# Lily_Pad_VGA_Fly_v1_01.net
KiCad netlist of a schematic drawn in EAGLE
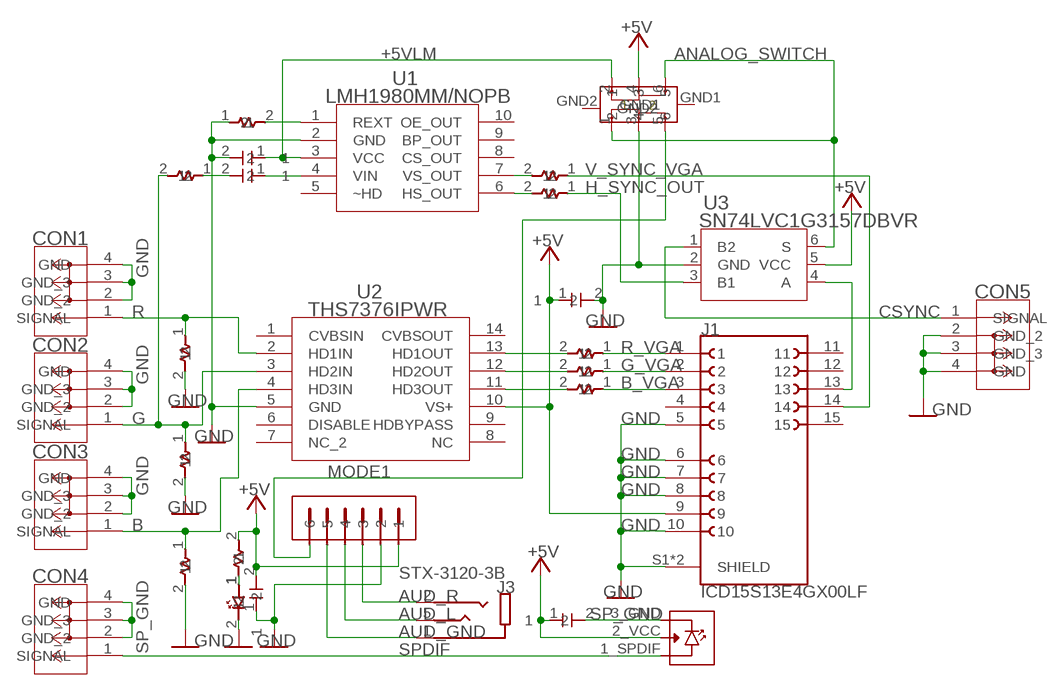
[diagram p0: schematic, sheet 1]

(export (version "E")
  (design (tool "Eeschema 10.0.6"))
  (components
    (comp (ref "C1")
      (value "22UF")
      (footprint "eagle-import:CAPACITOR_SMT_0603")
      (libsource (lib "eagle-import") (part "CAPACITOR0603"))
    )
    (comp (ref "C2")
      (value "0.1UF")
      (footprint "eagle-import:CAPACITOR_SMT_0603")
      (libsource (lib "eagle-import") (part "CAPACITOR0603"))
    )
    (comp (ref "C3")
      (value "0.1UF")
      (footprint "eagle-import:CAPACITOR_SMT_0603")
      (libsource (lib "eagle-import") (part "CAPACITOR0603"))
    )
    (comp (ref "C4")
      (value "0.1UF")
      (footprint "eagle-import:CAPACITOR_SMT_0603")
      (libsource (lib "eagle-import") (part "CAPACITOR0603"))
    )
    (comp (ref "C5")
      (value "0.1UF")
      (footprint "eagle-import:CAPACITOR_SMT_0603")
      (libsource (lib "eagle-import") (part "CAPACITOR0603"))
    )
    (comp (ref "CON1")
      (value "CONMHF1-SMD-G-T")
      (footprint "eagle-import:COAX3_CONMHF1-SMD-G-T_TEC")
      (fields (field (name "COPYRIGHT") "Copyright (C) 2024 Ultra Librarian. All rights reserved."))
      (libsource (lib "eagle-import") (part "CONMHF1-SMD-G-T"))
    )
    (comp (ref "CON2")
      (value "CONMHF1-SMD-G-T")
      (footprint "eagle-import:COAX3_CONMHF1-SMD-G-T_TEC")
      (fields (field (name "COPYRIGHT") "Copyright (C) 2024 Ultra Librarian. All rights reserved."))
      (libsource (lib "eagle-import") (part "CONMHF1-SMD-G-T"))
    )
    (comp (ref "CON3")
      (value "CONMHF1-SMD-G-T")
      (footprint "eagle-import:COAX3_CONMHF1-SMD-G-T_TEC")
      (fields (field (name "COPYRIGHT") "Copyright (C) 2024 Ultra Librarian. All rights reserved."))
      (libsource (lib "eagle-import") (part "CONMHF1-SMD-G-T"))
    )
    (comp (ref "CON4")
      (value "CONMHF1-SMD-G-T")
      (footprint "eagle-import:COAX3_CONMHF1-SMD-G-T_TEC")
      (fields (field (name "COPYRIGHT") "Copyright (C) 2024 Ultra Librarian. All rights reserved."))
      (libsource (lib "eagle-import") (part "CONMHF1-SMD-G-T"))
    )
    (comp (ref "CON5")
      (value "CONMHF1-SMD-G-T")
      (footprint "eagle-import:COAX3_CONMHF1-SMD-G-T_TEC")
      (fields (field (name "COPYRIGHT") "Copyright (C) 2024 Ultra Librarian. All rights reserved."))
      (libsource (lib "eagle-import") (part "CONMHF1-SMD-G-T"))
    )
    (comp (ref "J1")
      (value "ICD15S13E4GX00LF")
      (footprint "eagle-import:ICD15S13E4GX00LF")
      (fields (field (name "MANUFACTURER") "Amphenol"))
      (libsource (lib "eagle-import") (part "ICD15S13E4GX00LF"))
    )
    (comp (ref "J2")
      (value "0530470610")
      (footprint "eagle-import:0530470610")
      (libsource (lib "eagle-import") (part "0530470610"))
    )
    (comp (ref "J3")
      (value "STX-3120-3B")
      (footprint "eagle-import:KYCON_STX-3120-3B")
      (fields (field (name "MANUFACTURER") "KYCON"))
      (libsource (lib "eagle-import") (part "STX-3120-3B"))
    )
    (comp (ref "J4")
      (value "GQ-1504_OPTICAL")
      (footprint "eagle-import:GQ-1504_OPTICAL")
      (libsource (lib "eagle-import") (part "GQ-1504_OPTICAL"))
    )
    (comp (ref "LED1")
      (value "LED")
      (footprint "eagle-import:LED_SMT_0603")
      (libsource (lib "eagle-import") (part "LED"))
    )
    (comp (ref "R1")
      (value "75R")
      (footprint "eagle-import:RESISTOR_SMT_0603")
      (libsource (lib "eagle-import") (part "RESISTOR0603"))
    )
    (comp (ref "R2")
      (value "75R")
      (footprint "eagle-import:RESISTOR_SMT_0603")
      (libsource (lib "eagle-import") (part "RESISTOR0603"))
    )
    (comp (ref "R3")
      (value "75R")
      (footprint "eagle-import:RESISTOR_SMT_0603")
      (libsource (lib "eagle-import") (part "RESISTOR0603"))
    )
    (comp (ref "R4")
      (value "75R")
      (footprint "eagle-import:RESISTOR_SMT_0603")
      (libsource (lib "eagle-import") (part "RESISTOR0603"))
    )
    (comp (ref "R5")
      (value "75R")
      (footprint "eagle-import:RESISTOR_SMT_0603")
      (libsource (lib "eagle-import") (part "RESISTOR0603"))
    )
    (comp (ref "R6")
      (value "75R")
      (footprint "eagle-import:RESISTOR_SMT_0603")
      (libsource (lib "eagle-import") (part "RESISTOR0603"))
    )
    (comp (ref "R7")
      (value "91R")
      (footprint "eagle-import:RESISTOR_SMT_0603")
      (libsource (lib "eagle-import") (part "RESISTOR0603"))
    )
    (comp (ref "R8")
      (value "100R")
      (footprint "eagle-import:RESISTOR_SMT_0603")
      (libsource (lib "eagle-import") (part "RESISTOR0603"))
    )
    (comp (ref "R9")
      (value "100R")
      (footprint "eagle-import:RESISTOR_SMT_0603")
      (libsource (lib "eagle-import") (part "RESISTOR0603"))
    )
    (comp (ref "RA")
      (value "1K")
      (footprint "eagle-import:RESISTOR_SMT_0603")
      (libsource (lib "eagle-import") (part "RESISTOR0603"))
    )
    (comp (ref "RB")
      (value "10K")
      (footprint "eagle-import:RESISTOR_SMT_0603")
      (libsource (lib "eagle-import") (part "RESISTOR0603"))
    )
    (comp (ref "SW1")
      (value "DPDT_SW_SK22D07")
      (footprint "eagle-import:DPDT_SK22D07")
      (libsource (lib "eagle-import") (part "DPDT_SW_SK22D07"))
    )
    (comp (ref "U1")
      (value "LMH1980MM/NOPB")
      (footprint "eagle-import:MUB10A")
      (fields (field (name "COPYRIGHT") "Copyright (C) 2024 Ultra Librarian. All rights reserved."))
      (libsource (lib "eagle-import") (part "LMH1980MM/NOPB"))
    )
    (comp (ref "U2")
      (value "THS7376IPWR")
      (footprint "eagle-import:PW14_TEX")
      (fields (field (name "COPYRIGHT") "Copyright (C) 2024 Ultra Librarian. All rights reserved."))
      (libsource (lib "eagle-import") (part "THS7376IPWR"))
    )
    (comp (ref "U3")
      (value "SN74LVC1G3157DBVR")
      (footprint "eagle-import:DBV6")
      (fields (field (name "COPYRIGHT") "Copyright (C) 2025 Ultra Librarian. All rights reserved."))
      (libsource (lib "eagle-import") (part "SN74LVC1G3157DBVR"))
    )
  )
  (nets
    (net (code "1") (name "+5V") (class "Default")
      (node (ref "C1") (pin "2") (pinfunction "2_2") (pintype "bidirectional"))
      (node (ref "C4") (pin "1") (pinfunction "1_1") (pintype "bidirectional"))
      (node (ref "C5") (pin "1") (pinfunction "1_1") (pintype "bidirectional"))
      (node (ref "J1") (pin "9") (pinfunction "9_9") (pintype "passive"))
      (node (ref "J2") (pin "1") (pinfunction "1_1") (pintype "bidirectional"))
      (node (ref "J4") (pin "2_VCC") (pinfunction "2_VCC_2_VCC") (pintype "bidirectional"))
      (node (ref "RA") (pin "2") (pinfunction "2_2") (pintype "bidirectional"))
      (node (ref "SW1") (pin "4") (pinfunction "4_4") (pintype "bidirectional"))
      (node (ref "U2") (pin "10") (pinfunction "VS+_10") (pintype "power_in"))
      (node (ref "U3") (pin "5") (pinfunction "VCC_5") (pintype "power_in"))
    )
    (net (code "2") (name "/+5VLM") (class "Default")
      (node (ref "C2") (pin "1") (pinfunction "1_1") (pintype "bidirectional"))
      (node (ref "SW1") (pin "2") (pinfunction "2_2") (pintype "bidirectional"))
      (node (ref "U1") (pin "3") (pinfunction "VCC_3") (pintype "power_in"))
    )
    (net (code "3") (name "/ANALOG_SWITCH") (class "Default")
      (node (ref "SW1") (pin "1") (pinfunction "1_1") (pintype "bidirectional"))
      (node (ref "SW1") (pin "6") (pinfunction "6_6") (pintype "bidirectional"))
      (node (ref "U3") (pin "6") (pinfunction "S_6") (pintype "input"))
    )
    (net (code "4") (name "/AUD_GND") (class "Default")
      (node (ref "J2") (pin "5") (pinfunction "5_5") (pintype "bidirectional"))
      (node (ref "J3") (pin "1") (pinfunction "1_1") (pintype "passive"))
    )
    (net (code "5") (name "/AUD_L") (class "Default")
      (node (ref "J2") (pin "4") (pinfunction "4_4") (pintype "bidirectional"))
      (node (ref "J3") (pin "5") (pinfunction "5_5") (pintype "passive"))
    )
    (net (code "6") (name "/AUD_R") (class "Default")
      (node (ref "J2") (pin "3") (pinfunction "3_3") (pintype "bidirectional"))
      (node (ref "J3") (pin "2") (pinfunction "2_2") (pintype "passive"))
    )
    (net (code "7") (name "/B") (class "Default")
      (node (ref "CON3") (pin "1") (pinfunction "SIGNAL_1") (pintype "passive"))
      (node (ref "R1") (pin "1") (pinfunction "1_1") (pintype "bidirectional"))
      (node (ref "U2") (pin "4") (pinfunction "HD3IN_4") (pintype "input"))
    )
    (net (code "8") (name "/B_VGA") (class "Default")
      (node (ref "J1") (pin "3") (pinfunction "3_3") (pintype "passive"))
      (node (ref "R4") (pin "1") (pinfunction "1_1") (pintype "bidirectional"))
    )
    (net (code "9") (name "/CSYNC") (class "Default")
      (node (ref "CON5") (pin "1") (pinfunction "SIGNAL_1") (pintype "passive"))
      (node (ref "U3") (pin "1") (pinfunction "B2_1") (pintype "input"))
    )
    (net (code "10") (name "/G") (class "Default")
      (node (ref "CON2") (pin "1") (pinfunction "SIGNAL_1") (pintype "passive"))
      (node (ref "R2") (pin "1") (pinfunction "1_1") (pintype "bidirectional"))
      (node (ref "R8") (pin "2") (pinfunction "2_2") (pintype "bidirectional"))
      (node (ref "U2") (pin "3") (pinfunction "HD2IN_3") (pintype "input"))
    )
    (net (code "11") (name "/G_VGA") (class "Default")
      (node (ref "J1") (pin "2") (pinfunction "2_2") (pintype "passive"))
      (node (ref "R5") (pin "1") (pinfunction "1_1") (pintype "bidirectional"))
    )
    (net (code "12") (name "/H_SYNC_OUT") (class "Default")
      (node (ref "R7") (pin "1") (pinfunction "1_1") (pintype "bidirectional"))
      (node (ref "U3") (pin "3") (pinfunction "B1_3") (pintype "input"))
    )
    (net (code "13") (name "/MODE1") (class "Default")
      (node (ref "J2") (pin "6") (pinfunction "6_6") (pintype "bidirectional"))
      (node (ref "SW1") (pin "5") (pinfunction "5_5") (pintype "bidirectional"))
    )
    (net (code "14") (name "/R") (class "Default")
      (node (ref "CON1") (pin "1") (pinfunction "SIGNAL_1") (pintype "passive"))
      (node (ref "R3") (pin "1") (pinfunction "1_1") (pintype "bidirectional"))
      (node (ref "U2") (pin "2") (pinfunction "HD1IN_2") (pintype "input"))
    )
    (net (code "15") (name "/R_VGA") (class "Default")
      (node (ref "J1") (pin "1") (pinfunction "1_1") (pintype "passive"))
      (node (ref "R6") (pin "1") (pinfunction "1_1") (pintype "bidirectional"))
    )
    (net (code "16") (name "/SPDIF") (class "Default")
      (node (ref "CON4") (pin "1") (pinfunction "SIGNAL_1") (pintype "passive"))
      (node (ref "J4") (pin "1_SPDIF") (pinfunction "1_SPDIF_1_SPDIF") (pintype "bidirectional"))
    )
    (net (code "17") (name "/SP_GND") (class "Default")
      (node (ref "C5") (pin "2") (pinfunction "2_2") (pintype "bidirectional"))
      (node (ref "CON4") (pin "2") (pinfunction "GND_2_2") (pintype "passive"))
      (node (ref "CON4") (pin "3") (pinfunction "GND_3_3") (pintype "passive"))
      (node (ref "CON4") (pin "4") (pinfunction "GND_4") (pintype "passive"))
      (node (ref "J4") (pin "3_GND") (pinfunction "3_GND_3_GND") (pintype "bidirectional"))
    )
    (net (code "18") (name "/V_SYNC_VGA") (class "Default")
      (node (ref "J1") (pin "14") (pinfunction "14_14") (pintype "passive"))
      (node (ref "R9") (pin "1") (pinfunction "1_1") (pintype "bidirectional"))
    )
    (net (code "19") (name "GND") (class "Default")
      (node (ref "C1") (pin "1") (pinfunction "1_1") (pintype "bidirectional"))
      (node (ref "C2") (pin "2") (pinfunction "2_2") (pintype "bidirectional"))
      (node (ref "C4") (pin "2") (pinfunction "2_2") (pintype "bidirectional"))
      (node (ref "CON1") (pin "2") (pinfunction "GND_2_2") (pintype "passive"))
      (node (ref "CON1") (pin "3") (pinfunction "GND_3_3") (pintype "passive"))
      (node (ref "CON1") (pin "4") (pinfunction "GND_4") (pintype "passive"))
      (node (ref "CON2") (pin "2") (pinfunction "GND_2_2") (pintype "passive"))
      (node (ref "CON2") (pin "3") (pinfunction "GND_3_3") (pintype "passive"))
      (node (ref "CON2") (pin "4") (pinfunction "GND_4") (pintype "passive"))
      (node (ref "CON3") (pin "2") (pinfunction "GND_2_2") (pintype "passive"))
      (node (ref "CON3") (pin "3") (pinfunction "GND_3_3") (pintype "passive"))
      (node (ref "CON3") (pin "4") (pinfunction "GND_4") (pintype "passive"))
      (node (ref "CON5") (pin "2") (pinfunction "GND_2_2") (pintype "passive"))
      (node (ref "CON5") (pin "3") (pinfunction "GND_3_3") (pintype "passive"))
      (node (ref "CON5") (pin "4") (pinfunction "GND_4") (pintype "passive"))
      (node (ref "J1") (pin "10") (pinfunction "10_10") (pintype "passive"))
      (node (ref "J1") (pin "5") (pinfunction "5_5") (pintype "passive"))
      (node (ref "J1") (pin "6") (pinfunction "6_6") (pintype "passive"))
      (node (ref "J1") (pin "7") (pinfunction "7_7") (pintype "passive"))
      (node (ref "J1") (pin "8") (pinfunction "8_8") (pintype "passive"))
      (node (ref "J1") (pin "S1") (pinfunction "SHIELD_S1") (pintype "passive"))
      (node (ref "J1") (pin "S2") (pinfunction "SHIELD_S2") (pintype "passive"))
      (node (ref "J2") (pin "2") (pinfunction "2_2") (pintype "bidirectional"))
      (node (ref "LED1") (pin "2") (pinfunction "2_2") (pintype "bidirectional"))
      (node (ref "R1") (pin "2") (pinfunction "2_2") (pintype "bidirectional"))
      (node (ref "R2") (pin "2") (pinfunction "2_2") (pintype "bidirectional"))
      (node (ref "R3") (pin "2") (pinfunction "2_2") (pintype "bidirectional"))
      (node (ref "RB") (pin "1") (pinfunction "1_1") (pintype "bidirectional"))
      (node (ref "SW1") (pin "3") (pinfunction "3_3") (pintype "bidirectional"))
      (node (ref "U1") (pin "2") (pinfunction "GND_2") (pintype "power_in"))
      (node (ref "U2") (pin "5") (pinfunction "GND_5") (pintype "power_in"))
      (node (ref "U3") (pin "2") (pinfunction "GND_2") (pintype "power_in"))
    )
    (net (code "20") (name "Net-(C3-Pad2)") (class "Default")
      (node (ref "C3") (pin "2") (pinfunction "2_2") (pintype "bidirectional"))
      (node (ref "R8") (pin "1") (pinfunction "1_1") (pintype "bidirectional"))
    )
    (net (code "21") (name "Net-(LED1-Pad1)") (class "Default")
      (node (ref "LED1") (pin "1") (pinfunction "1_1") (pintype "bidirectional"))
      (node (ref "RA") (pin "1") (pinfunction "1_1") (pintype "bidirectional"))
    )
    (net (code "22") (name "Net-(U1-HS_OUT)") (class "Default")
      (node (ref "R7") (pin "2") (pinfunction "2_2") (pintype "bidirectional"))
      (node (ref "U1") (pin "6") (pinfunction "HS_OUT_6") (pintype "output"))
    )
    (net (code "23") (name "Net-(U1-REXT)") (class "Default")
      (node (ref "RB") (pin "2") (pinfunction "2_2") (pintype "bidirectional"))
      (node (ref "U1") (pin "1") (pinfunction "REXT_1") (pintype "passive"))
    )
    (net (code "24") (name "Net-(U1-VIN)") (class "Default")
      (node (ref "C3") (pin "1") (pinfunction "1_1") (pintype "bidirectional"))
      (node (ref "U1") (pin "4") (pinfunction "VIN_4") (pintype "input"))
    )
    (net (code "25") (name "Net-(U1-VS_OUT)") (class "Default")
      (node (ref "R9") (pin "2") (pinfunction "2_2") (pintype "bidirectional"))
      (node (ref "U1") (pin "7") (pinfunction "VS_OUT_7") (pintype "output"))
    )
    (net (code "26") (name "Net-(U2-HD1OUT)") (class "Default")
      (node (ref "R6") (pin "2") (pinfunction "2_2") (pintype "bidirectional"))
      (node (ref "U2") (pin "13") (pinfunction "HD1OUT_13") (pintype "output"))
    )
    (net (code "27") (name "Net-(U2-HD2OUT)") (class "Default")
      (node (ref "R5") (pin "2") (pinfunction "2_2") (pintype "bidirectional"))
      (node (ref "U2") (pin "12") (pinfunction "HD2OUT_12") (pintype "output"))
    )
    (net (code "28") (name "Net-(U2-HD3OUT)") (class "Default")
      (node (ref "R4") (pin "2") (pinfunction "2_2") (pintype "bidirectional"))
      (node (ref "U2") (pin "11") (pinfunction "HD3OUT_11") (pintype "output"))
    )
    (net (code "29") (name "Net-(U3-A)") (class "Default")
      (node (ref "J1") (pin "13") (pinfunction "13_13") (pintype "passive"))
      (node (ref "U3") (pin "4") (pinfunction "A_4") (pintype "input"))
    )
    (net (code "30") (name "unconnected-(J1-Pad4)") (class "Default")
      (node (ref "J1") (pin "4") (pinfunction "4_4") (pintype "passive"))
    )
    (net (code "31") (name "unconnected-(J1-Pad11)") (class "Default")
      (node (ref "J1") (pin "11") (pinfunction "11_11") (pintype "passive"))
    )
    (net (code "32") (name "unconnected-(J1-Pad12)") (class "Default")
      (node (ref "J1") (pin "12") (pinfunction "12_12") (pintype "passive"))
    )
    (net (code "33") (name "unconnected-(J1-Pad15)") (class "Default")
      (node (ref "J1") (pin "15") (pinfunction "15_15") (pintype "passive"))
    )
    (net (code "34") (name "unconnected-(SW1-PadGND1)") (class "Default")
      (node (ref "SW1") (pin "GND1") (pinfunction "GND1_GND1") (pintype "bidirectional"))
    )
    (net (code "35") (name "unconnected-(SW1-PadGND2)") (class "Default")
      (node (ref "SW1") (pin "GND2") (pinfunction "GND2_GND2") (pintype "bidirectional"))
    )
    (net (code "36") (name "unconnected-(U1-BP_OUT-Pad9)") (class "Default")
      (node (ref "U1") (pin "9") (pinfunction "BP_OUT_9") (pintype "output"))
    )
    (net (code "37") (name "unconnected-(U1-CS_OUT-Pad8)") (class "Default")
      (node (ref "U1") (pin "8") (pinfunction "CS_OUT_8") (pintype "output"))
    )
    (net (code "38") (name "unconnected-(U1-OE_OUT-Pad10)") (class "Default")
      (node (ref "U1") (pin "10") (pinfunction "OE_OUT_10") (pintype "output"))
    )
    (net (code "39") (name "unconnected-(U1-~{HD}-Pad5)") (class "Default")
      (node (ref "U1") (pin "5") (pinfunction "~{HD}_5") (pintype "output"))
    )
    (net (code "40") (name "unconnected-(U2-CVBSIN-Pad1)") (class "Default")
      (node (ref "U2") (pin "1") (pinfunction "CVBSIN_1") (pintype "input"))
    )
    (net (code "41") (name "unconnected-(U2-CVBSOUT-Pad14)") (class "Default")
      (node (ref "U2") (pin "14") (pinfunction "CVBSOUT_14") (pintype "output"))
    )
    (net (code "42") (name "unconnected-(U2-DISABLE-Pad6)") (class "Default")
      (node (ref "U2") (pin "6") (pinfunction "DISABLE_6") (pintype "input"))
    )
    (net (code "43") (name "unconnected-(U2-HDBYPASS-Pad9)") (class "Default")
      (node (ref "U2") (pin "9") (pinfunction "HDBYPASS_9") (pintype "input"))
    )
    (net (code "44") (name "unconnected-(U2-NC-Pad8)") (class "Default")
      (node (ref "U2") (pin "8") (pinfunction "NC_8") (pintype "no_connect"))
    )
    (net (code "45") (name "unconnected-(U2-NC_2-Pad7)") (class "Default")
      (node (ref "U2") (pin "7") (pinfunction "NC_2_7") (pintype "no_connect"))
    )
  )
)
